# H1DR00.net
KiCad netlist of a schematic drawn in EAGLE
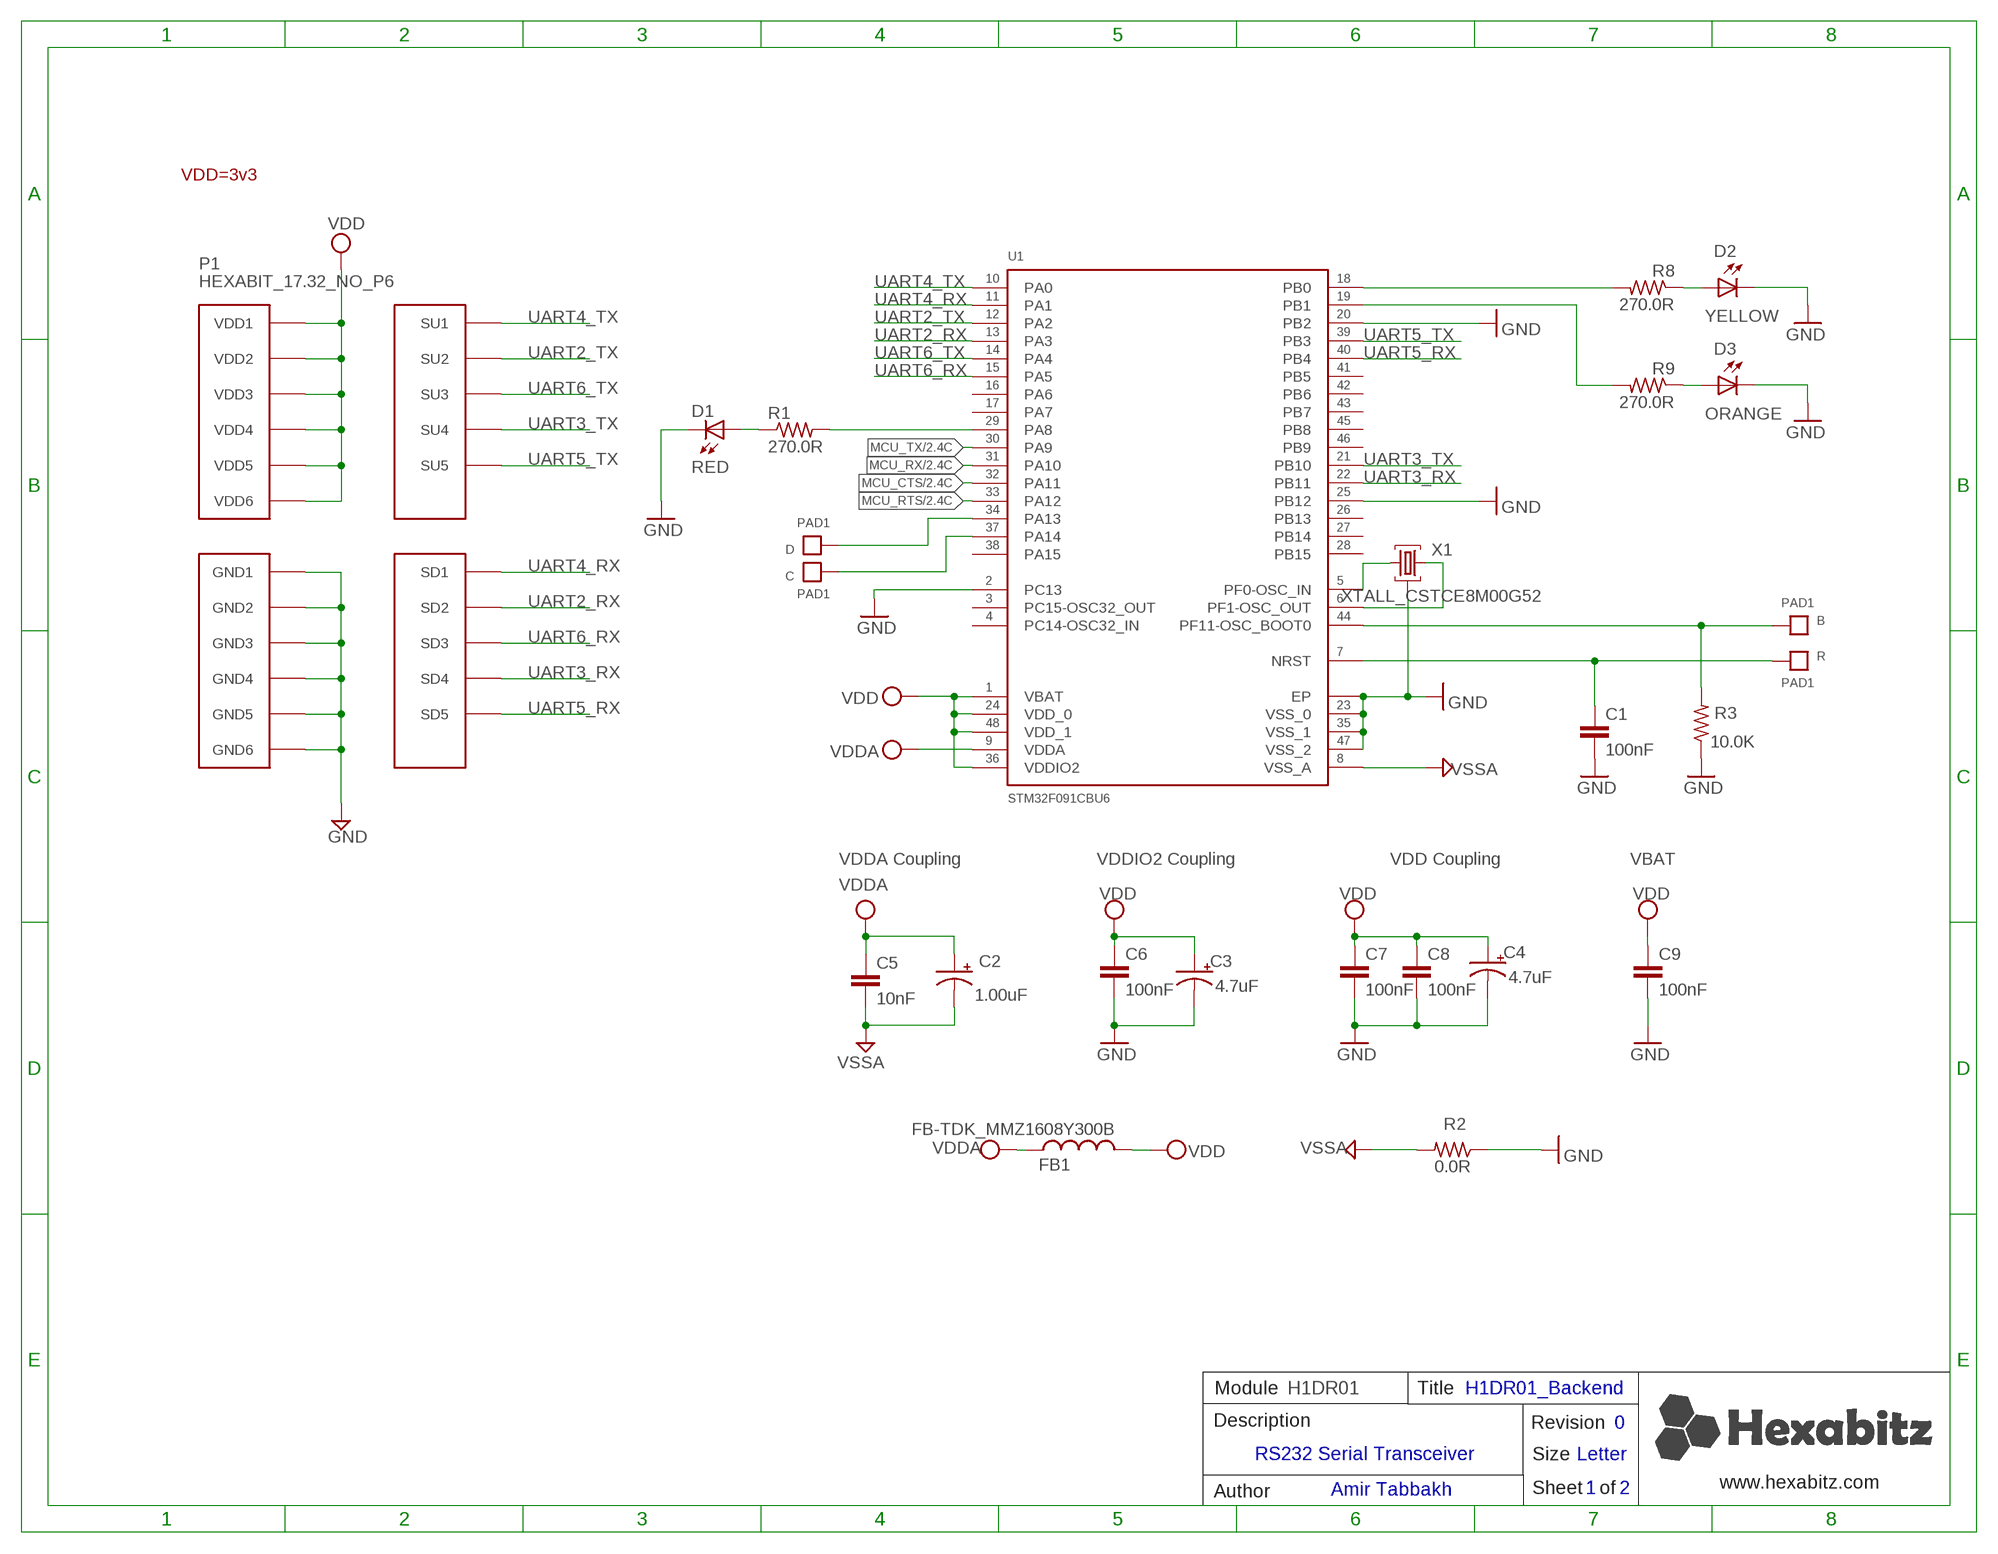
[diagram p0: schematic, sheet 1]
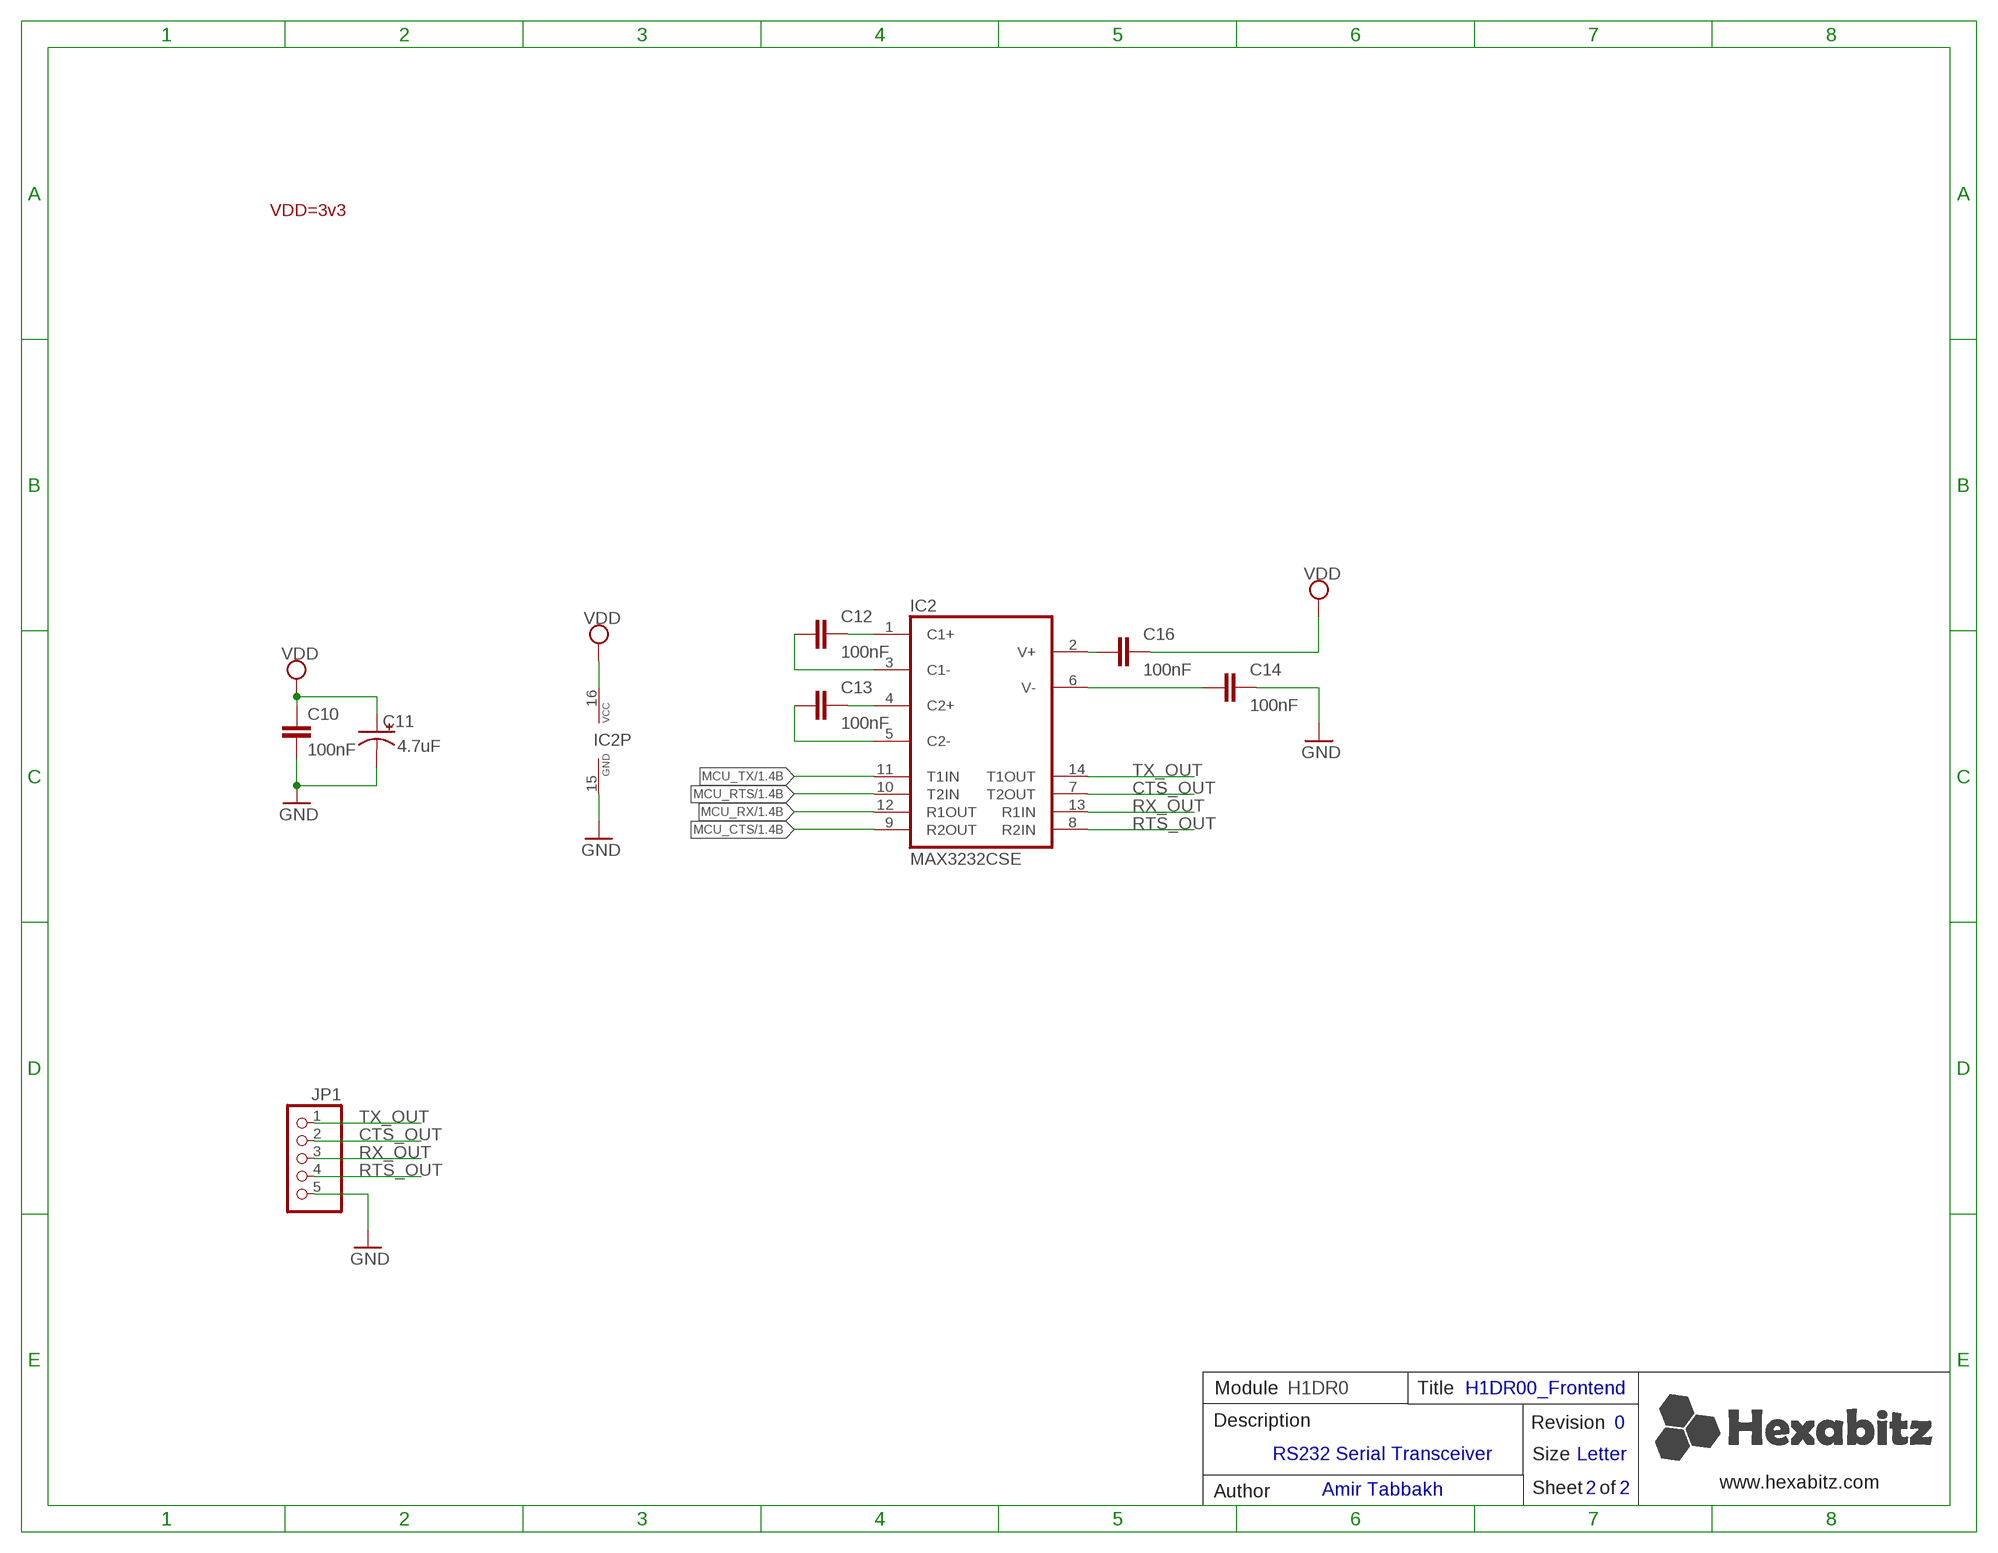
[diagram p1: schematic, sheet 2]

(export (version "E")
  (design (tool "Eeschema 10.0.6"))
  (components
    (comp (ref "C10")
      (value "100nF")
      (footprint "eagle-import:C-0603")
      (fields
        (field (name "CAPACITANCE") "100nF")
        (field (name "MFN") "KEMET")
        (field (name "MPN") "C0603C104K8RACTU")
        (field (name "OCTOPART_URL") "https://octopart.com/c0603c104k8ractu-kemet-145075?r=sp&s=9bS9ASSwSEqMCE9KBEQZ0g")
        (field (name "TOLERANCE") "10%")
        (field (name "VOLTAGE_RATING") "10V")
      )
      (libsource (lib "eagle-import") (part "C-0603"))
    )
    (comp (ref "C11")
      (value "4.7uF")
      (footprint "eagle-import:C-0805-POL")
      (fields
        (field (name "CAPACITANCE") "4.7uF")
        (field (name "MFN") "Murata")
        (field (name "MPN") "GRM21BC81E475KA12L")
        (field (name "OCTOPART_URL") "https://octopart.com/grm21bc81e475ka12l-murata-10331911?r=sp&s=RY3qZSD8T6mG6TC9CHI5qQ")
        (field (name "TOLERANCE") "10%")
        (field (name "VOLTAGE_RATING") "25V")
      )
      (libsource (lib "eagle-import") (part "C-0805-POL"))
    )
    (comp (ref "C12")
      (value "100nF")
      (footprint "eagle-import:C-0603")
      (fields
        (field (name "CAPACITANCE") "100nF")
        (field (name "MFN") "KEMET")
        (field (name "MPN") "C0603C104K8RACTU")
        (field (name "OCTOPART_URL") "https://octopart.com/c0603c104k8ractu-kemet-145075?r=sp&s=9bS9ASSwSEqMCE9KBEQZ0g")
        (field (name "TOLERANCE") "10%")
        (field (name "VOLTAGE_RATING") "10")
      )
      (libsource (lib "eagle-import") (part "C-0603"))
    )
    (comp (ref "C13")
      (value "100nF")
      (footprint "eagle-import:C-0603")
      (fields
        (field (name "CAPACITANCE") "100nF")
        (field (name "MFN") "KEMET")
        (field (name "MPN") "C0603C104K8RACTU")
        (field (name "OCTOPART_URL") "https://octopart.com/c0603c104k8ractu-kemet-145075?r=sp&s=9bS9ASSwSEqMCE9KBEQZ0g")
        (field (name "TOLERANCE") "10%")
        (field (name "VOLTAGE_RATING") "10")
      )
      (libsource (lib "eagle-import") (part "C-0603"))
    )
    (comp (ref "C14")
      (value "100nF")
      (footprint "eagle-import:C-0603")
      (fields
        (field (name "CAPACITANCE") "100nF")
        (field (name "MFN") "KEMET")
        (field (name "MPN") "C0603C104K8RACTU")
        (field (name "OCTOPART_URL") "https://octopart.com/c0603c104k8ractu-kemet-145075?r=sp&s=9bS9ASSwSEqMCE9KBEQZ0g")
        (field (name "TOLERANCE") "10%")
        (field (name "VOLTAGE_RATING") "10")
      )
      (libsource (lib "eagle-import") (part "C-0603"))
    )
    (comp (ref "C16")
      (value "100nF")
      (footprint "eagle-import:C-0603")
      (fields
        (field (name "CAPACITANCE") "100nF")
        (field (name "MFN") "KEMET")
        (field (name "MPN") "C0603C104K8RACTU")
        (field (name "OCTOPART_URL") "https://octopart.com/c0603c104k8ractu-kemet-145075?r=sp&s=9bS9ASSwSEqMCE9KBEQZ0g")
        (field (name "TOLERANCE") "10%")
        (field (name "VOLTAGE_RATING") "10")
      )
      (libsource (lib "eagle-import") (part "C-0603"))
    )
    (comp (ref "IC2")
      (value "MAX3232CSE")
      (footprint "eagle-import:SO16")
      (libsource (lib "eagle-import") (part "MAX3232SEC"))
    )
    (comp (ref "JP1")
      (value "PINHD-1X5/90")
      (footprint "eagle-import:1X05_90")
      (libsource (lib "eagle-import") (part "PINHD-1X5/90"))
    )
    (comp (ref "B")
      (value "PAD1")
      (footprint "eagle-import:PAD1")
      (libsource (lib "eagle-import") (part "PAD1"))
    )
    (comp (ref "C")
      (value "PAD1")
      (footprint "eagle-import:PAD1")
      (libsource (lib "eagle-import") (part "PAD1"))
    )
    (comp (ref "C1")
      (value "100nF")
      (footprint "eagle-import:C-0603")
      (fields
        (field (name "CAPACITANCE") "100nF")
        (field (name "MFN") "KEMET")
        (field (name "MPN") "C0603C104K8RACTU")
        (field (name "OCTOPART_URL") "https://octopart.com/c0603c104k8ractu-kemet-145075?r=sp&s=9bS9ASSwSEqMCE9KBEQZ0g")
        (field (name "TOLERANCE") "10%")
        (field (name "VOLTAGE_RATING") "10V")
      )
      (libsource (lib "eagle-import") (part "C-0603"))
    )
    (comp (ref "C2")
      (value "1.00uF")
      (footprint "eagle-import:C-0805-POL")
      (fields
        (field (name "CAPACITANCE") "1.00uF")
        (field (name "MFN") "Yageo")
        (field (name "MPN") "CC0805KKX7R7BB105")
        (field (name "OCTOPART_URL") "https://octopart.com/cc0805kkx7r7bb105-yageo-8376555?r=sp&s=YKl1wwtkROau_X5nniH2ig")
        (field (name "TOLERANCE") "10%")
        (field (name "VOLTAGE_RATING") "16V")
      )
      (libsource (lib "eagle-import") (part "C-0805-POL"))
    )
    (comp (ref "C3")
      (value "4.7uF")
      (footprint "eagle-import:C-0805-POL")
      (fields
        (field (name "CAPACITANCE") "4.7uF")
        (field (name "MFN") "Murata")
        (field (name "MPN") "GRM21BC81E475KA12L")
        (field (name "OCTOPART_URL") "https://octopart.com/grm21bc81e475ka12l-murata-10331911?r=sp&s=RY3qZSD8T6mG6TC9CHI5qQ")
        (field (name "TOLERANCE") "10%")
        (field (name "VOLTAGE_RATING") "25V")
      )
      (libsource (lib "eagle-import") (part "C-0805-POL"))
    )
    (comp (ref "C4")
      (value "4.7uF")
      (footprint "eagle-import:C-0805-POL")
      (fields
        (field (name "CAPACITANCE") "4.7uF")
        (field (name "MFN") "Murata")
        (field (name "MPN") "GRM21BC81E475KA12L")
        (field (name "OCTOPART_URL") "https://octopart.com/grm21bc81e475ka12l-murata-10331911?r=sp&s=RY3qZSD8T6mG6TC9CHI5qQ")
        (field (name "TOLERANCE") "10%")
        (field (name "VOLTAGE_RATING") "25V")
      )
      (libsource (lib "eagle-import") (part "C-0805-POL"))
    )
    (comp (ref "C5")
      (value "10nF")
      (footprint "eagle-import:C-0603")
      (fields
        (field (name "CAPACITANCE") "10nF")
        (field (name "MFN") "KEMET")
        (field (name "MPN") "C0603C103K5RACTU")
        (field (name "OCTOPART_URL") "https://octopart.com/c0603c103k5ractu-kemet-133094?r=sp&s=R_iPBxLnSmGqhkU2rIMFpg")
        (field (name "TOLERANCE") "10%")
        (field (name "VOLTAGE_RATING") "50V")
      )
      (libsource (lib "eagle-import") (part "C-0603"))
    )
    (comp (ref "C6")
      (value "100nF")
      (footprint "eagle-import:C-0603")
      (fields
        (field (name "CAPACITANCE") "100nF")
        (field (name "MFN") "KEMET")
        (field (name "MPN") "C0603C104K8RACTU")
        (field (name "OCTOPART_URL") "https://octopart.com/c0603c104k8ractu-kemet-145075?r=sp&s=9bS9ASSwSEqMCE9KBEQZ0g")
        (field (name "TOLERANCE") "10%")
        (field (name "VOLTAGE_RATING") "10V")
      )
      (libsource (lib "eagle-import") (part "C-0603"))
    )
    (comp (ref "C7")
      (value "100nF")
      (footprint "eagle-import:C-0603")
      (fields
        (field (name "CAPACITANCE") "100nF")
        (field (name "MFN") "KEMET")
        (field (name "MPN") "C0603C104K8RACTU")
        (field (name "OCTOPART_URL") "https://octopart.com/c0603c104k8ractu-kemet-145075?r=sp&s=9bS9ASSwSEqMCE9KBEQZ0g")
        (field (name "TOLERANCE") "10%")
        (field (name "VOLTAGE_RATING") "10")
      )
      (libsource (lib "eagle-import") (part "C-0603"))
    )
    (comp (ref "C8")
      (value "100nF")
      (footprint "eagle-import:C-0603")
      (fields
        (field (name "CAPACITANCE") "100nF")
        (field (name "MFN") "KEMET")
        (field (name "MPN") "C0603C104K8RACTU")
        (field (name "OCTOPART_URL") "https://octopart.com/c0603c104k8ractu-kemet-145075?r=sp&s=9bS9ASSwSEqMCE9KBEQZ0g")
        (field (name "TOLERANCE") "10%")
        (field (name "VOLTAGE_RATING") "10V")
      )
      (libsource (lib "eagle-import") (part "C-0603"))
    )
    (comp (ref "C9")
      (value "100nF")
      (footprint "eagle-import:C-0603")
      (fields
        (field (name "CAPACITANCE") "100nF")
        (field (name "MFN") "KEMET")
        (field (name "MPN") "C0603C104K8RACTU")
        (field (name "OCTOPART_URL") "https://octopart.com/c0603c104k8ractu-kemet-145075?r=sp&s=9bS9ASSwSEqMCE9KBEQZ0g")
        (field (name "TOLERANCE") "10V")
        (field (name "VOLTAGE_RATING") "10%")
      )
      (libsource (lib "eagle-import") (part "C-0603"))
    )
    (comp (ref "D")
      (value "PAD1")
      (footprint "eagle-import:PAD1")
      (libsource (lib "eagle-import") (part "PAD1"))
    )
    (comp (ref "D1")
      (value "RED")
      (footprint "eagle-import:VLMS1300-GS08")
      (fields
        (field (name "MPN") "VLMS1300-GS08")
        (field (name "MFN") "Vishay")
        (field (name "MPN_1") "VLMS1300-GS08")
        (field (name "OCTOPART_URL") "https://octopart.com/vlms1300-gs08-vishay-21709201?r=sp&s=_gcP4_q8T1SC6PJQPTQ9yA")
      )
      (libsource (lib "eagle-import") (part "VLMS1300-GS08"))
    )
    (comp (ref "D2")
      (value "YELLOW")
      (footprint "eagle-import:VLMS1300-GS08")
      (fields
        (field (name "MPN") "VLMS1300-GS08")
        (field (name "MFN") "Vishay")
        (field (name "MPN_1") "VLMY1300-GS08")
        (field (name "OCTOPART_URL") "https://octopart.com/vlmy1300-gs08-vishay-21709204?r=sp")
      )
      (libsource (lib "eagle-import") (part "VLMS1300-GS08"))
    )
    (comp (ref "D3")
      (value "ORANGE")
      (footprint "eagle-import:VLMS1300-GS08")
      (fields
        (field (name "MPN") "VLMS1300-GS08")
        (field (name "MFN") "Vishay")
        (field (name "MPN_1") "VLMO1300-GS08 ")
        (field (name "OCTOPART_URL") "https://octopart.com/vlmo1300-gs08-vishay-21709200?r=sp#")
      )
      (libsource (lib "eagle-import") (part "VLMS1300-GS08"))
    )
    (comp (ref "FB1")
      (value "FB-TDK_MMZ1608Y300B")
      (footprint "eagle-import:FB-TDK_MMZ1608Y300B")
      (fields
        (field (name "MFN") "TDK ")
        (field (name "MPN") "MMZ1608Y300B")
        (field (name "OCTOPART_URL") "https://octopart.com/mmz1608y300b-tdk-368280?r=sp&s=cd9_2ZEqQ9q9UNBuQgHAiA")
      )
      (libsource (lib "eagle-import") (part "FB-TDK_MMZ1608Y300B"))
    )
    (comp (ref "P1")
      (value "HEXABIT_17.32_NO_P6")
      (footprint "eagle-import:HEXABIT_17.32_NO_P6")
      (libsource (lib "eagle-import") (part "HEXABIT_?_NO_P617.32"))
    )
    (comp (ref "R")
      (value "PAD1")
      (footprint "eagle-import:PAD1")
      (libsource (lib "eagle-import") (part "PAD1"))
    )
    (comp (ref "R1")
      (value "270.0R")
      (footprint "eagle-import:R-0603")
      (fields
        (field (name "MFN") "Yageo")
        (field (name "MPN") "RC0603FR-07270RL")
        (field (name "OCTOPART_URL") "https://octopart.com/search?q=RC0603FR-07270RL&start=0")
        (field (name "RESISTANCE") "270.0 Ohm")
        (field (name "TOLERANCE") "1%")
      )
      (libsource (lib "eagle-import") (part "R-0603"))
    )
    (comp (ref "R2")
      (value "0.0R")
      (footprint "eagle-import:R-0603")
      (fields
        (field (name "MFN") "Yageo")
        (field (name "MPN") "RC0603JR-070RL")
        (field (name "OCTOPART_URL") "https://octopart.com/rc0603jr-070rl-yageo-1241539?r=sp&s=X2NteqRjRNWrnx42Y0aliA")
        (field (name "RESISTANCE") "0.0 Ohm")
      )
      (libsource (lib "eagle-import") (part "R-0603"))
    )
    (comp (ref "R3")
      (value "10.0K")
      (footprint "eagle-import:R-0603")
      (fields
        (field (name "MFN") "Yageo")
        (field (name "MPN") "RC0603JR-0710KL")
        (field (name "OCTOPART_URL") "https://octopart.com/search?q=RC0603JR-0710KL&start=0")
        (field (name "RESISTANCE") "10.0K Ohm")
        (field (name "TOLERANCE") "5%")
      )
      (libsource (lib "eagle-import") (part "R-0603"))
    )
    (comp (ref "R8")
      (value "270.0R")
      (footprint "eagle-import:R-0603")
      (fields
        (field (name "MFN") "Yageo")
        (field (name "MPN") "RC0603FR-07270RL")
        (field (name "OCTOPART_URL") "https://octopart.com/search?q=RC0603FR-07270RL&start=0")
        (field (name "RESISTANCE") "270.0 Ohm")
        (field (name "TOLERANCE") "1%")
      )
      (libsource (lib "eagle-import") (part "R-0603"))
    )
    (comp (ref "R9")
      (value "270.0R")
      (footprint "eagle-import:R-0603")
      (fields
        (field (name "MFN") "Yageo")
        (field (name "MPN") "RC0603FR-07270RL")
        (field (name "OCTOPART_URL") "https://octopart.com/search?q=RC0603FR-07270RL&start=0")
        (field (name "RESISTANCE") "270.0 Ohm")
        (field (name "TOLERANCE") "1%")
      )
      (libsource (lib "eagle-import") (part "R-0603"))
    )
    (comp (ref "U1")
      (value "STM32F091CBU6")
      (footprint "eagle-import:STM32F091CBU6")
      (libsource (lib "eagle-import") (part "STM32F091CBU6"))
    )
    (comp (ref "X1")
      (value "XTALL_CSTCE8M00G52")
      (footprint "eagle-import:XTALL_CSTCE8M00G52")
      (fields (field (name "MPN") "CSTCE8M00G52Z-R0"))
      (libsource (lib "eagle-import") (part "XTALL_CSTCE8M00G52"))
    )
  )
  (nets
    (net (code "1") (name "CTS_OUT") (class "Default")
      (node (ref "IC2") (pin "7") (pinfunction "T2OUT_7") (pintype "output"))
      (node (ref "JP1") (pin "2") (pinfunction "2_2") (pintype "passive"))
    )
    (net (code "2") (name "GND") (class "Default")
      (node (ref "C1") (pin "2") (pinfunction "2_2") (pintype "passive"))
      (node (ref "C10") (pin "2") (pinfunction "2_2") (pintype "passive"))
      (node (ref "C11") (pin "2") (pinfunction "-_2") (pintype "passive"))
      (node (ref "C14") (pin "2") (pinfunction "2_2") (pintype "passive"))
      (node (ref "C3") (pin "2") (pinfunction "-_2") (pintype "passive"))
      (node (ref "C4") (pin "2") (pinfunction "-_2") (pintype "passive"))
      (node (ref "C6") (pin "2") (pinfunction "2_2") (pintype "passive"))
      (node (ref "C7") (pin "2") (pinfunction "2_2") (pintype "passive"))
      (node (ref "C8") (pin "2") (pinfunction "2_2") (pintype "passive"))
      (node (ref "C9") (pin "2") (pinfunction "2_2") (pintype "passive"))
      (node (ref "D1") (pin "C") (pinfunction "C_C") (pintype "passive"))
      (node (ref "D2") (pin "C") (pinfunction "C_C") (pintype "passive"))
      (node (ref "D3") (pin "C") (pinfunction "C_C") (pintype "passive"))
      (node (ref "IC2") (pin "15") (pinfunction "GND_15") (pintype "power_in"))
      (node (ref "JP1") (pin "5") (pinfunction "5_5") (pintype "passive"))
      (node (ref "P1") (pin "PAD_PD10") (pinfunction "GND4_PAD_PD10") (pintype "power_in"))
      (node (ref "P1") (pin "PAD_PD11") (pinfunction "GND5_PAD_PD11") (pintype "power_in"))
      (node (ref "P1") (pin "PAD_PD12") (pinfunction "GND6_PAD_PD12") (pintype "power_in"))
      (node (ref "P1") (pin "PAD_PD7") (pinfunction "GND1_PAD_PD7") (pintype "power_in"))
      (node (ref "P1") (pin "PAD_PD8") (pinfunction "GND2_PAD_PD8") (pintype "power_in"))
      (node (ref "P1") (pin "PAD_PD9") (pinfunction "GND3_PAD_PD9") (pintype "power_in"))
      (node (ref "R2") (pin "1") (pinfunction "1_1") (pintype "passive"))
      (node (ref "R3") (pin "1") (pinfunction "1_1") (pintype "passive"))
      (node (ref "U1") (pin "EP") (pinfunction "EP_EP") (pintype "power_in"))
      (node (ref "U1") (pin "P$2") (pinfunction "PC13_P$2") (pintype "bidirectional"))
      (node (ref "U1") (pin "P$20") (pinfunction "PB2_P$20") (pintype "bidirectional"))
      (node (ref "U1") (pin "P$23") (pinfunction "VSS_0_P$23") (pintype "power_in"))
      (node (ref "U1") (pin "P$25") (pinfunction "PB12_P$25") (pintype "bidirectional"))
      (node (ref "U1") (pin "P$35") (pinfunction "VSS_1_P$35") (pintype "power_in"))
      (node (ref "U1") (pin "P$47") (pinfunction "VSS_2_P$47") (pintype "power_in"))
      (node (ref "X1") (pin "P$2") (pinfunction "2_P$2") (pintype "passive"))
    )
    (net (code "3") (name "MCU_CTS") (class "Default")
      (node (ref "IC2") (pin "9") (pinfunction "R2OUT_9") (pintype "output"))
      (node (ref "U1") (pin "P$32") (pinfunction "PA11_P$32") (pintype "bidirectional"))
    )
    (net (code "4") (name "MCU_RTS") (class "Default")
      (node (ref "IC2") (pin "10") (pinfunction "T2IN_10") (pintype "input"))
      (node (ref "U1") (pin "P$33") (pinfunction "PA12_P$33") (pintype "bidirectional"))
    )
    (net (code "5") (name "MCU_RX") (class "Default")
      (node (ref "IC2") (pin "12") (pinfunction "R1OUT_12") (pintype "output"))
      (node (ref "U1") (pin "P$31") (pinfunction "PA10_P$31") (pintype "bidirectional"))
    )
    (net (code "6") (name "MCU_TX") (class "Default")
      (node (ref "IC2") (pin "11") (pinfunction "T1IN_11") (pintype "input"))
      (node (ref "U1") (pin "P$30") (pinfunction "PA9_P$30") (pintype "bidirectional"))
    )
    (net (code "7") (name "Net-(D1-PadA)") (class "Default")
      (node (ref "D1") (pin "A") (pinfunction "A_A") (pintype "passive"))
      (node (ref "R1") (pin "1") (pinfunction "1_1") (pintype "passive"))
    )
    (net (code "8") (name "Net-(D2-PadA)") (class "Default")
      (node (ref "D2") (pin "A") (pinfunction "A_A") (pintype "passive"))
      (node (ref "R8") (pin "1") (pinfunction "1_1") (pintype "passive"))
    )
    (net (code "9") (name "Net-(D3-PadA)") (class "Default")
      (node (ref "D3") (pin "A") (pinfunction "A_A") (pintype "passive"))
      (node (ref "R9") (pin "1") (pinfunction "1_1") (pintype "passive"))
    )
    (net (code "10") (name "Net-(IC2A-C1+)") (class "Default")
      (node (ref "C12") (pin "2") (pinfunction "2_2") (pintype "passive"))
      (node (ref "IC2") (pin "1") (pinfunction "C1+_1") (pintype "bidirectional"))
    )
    (net (code "11") (name "Net-(IC2A-C1-)") (class "Default")
      (node (ref "C12") (pin "1") (pinfunction "1_1") (pintype "passive"))
      (node (ref "IC2") (pin "3") (pinfunction "C1-_3") (pintype "bidirectional"))
    )
    (net (code "12") (name "Net-(IC2A-C2+)") (class "Default")
      (node (ref "C13") (pin "2") (pinfunction "2_2") (pintype "passive"))
      (node (ref "IC2") (pin "4") (pinfunction "C2+_4") (pintype "bidirectional"))
    )
    (net (code "13") (name "Net-(IC2A-C2-)") (class "Default")
      (node (ref "C13") (pin "1") (pinfunction "1_1") (pintype "passive"))
      (node (ref "IC2") (pin "5") (pinfunction "C2-_5") (pintype "bidirectional"))
    )
    (net (code "14") (name "Net-(IC2A-V+)") (class "Default")
      (node (ref "C16") (pin "1") (pinfunction "1_1") (pintype "passive"))
      (node (ref "IC2") (pin "2") (pinfunction "V+_2") (pintype "bidirectional"))
    )
    (net (code "15") (name "Net-(IC2A-V-)") (class "Default")
      (node (ref "C14") (pin "1") (pinfunction "1_1") (pintype "passive"))
      (node (ref "IC2") (pin "6") (pinfunction "V-_6") (pintype "bidirectional"))
    )
    (net (code "16") (name "Net-(U1-NRST)") (class "Default")
      (node (ref "C1") (pin "1") (pinfunction "1_1") (pintype "passive"))
      (node (ref "R") (pin "P$1") (pinfunction "P$1_P$1") (pintype "passive"))
      (node (ref "R") (pin "P$2") (pinfunction "P$1_P$2") (pintype "passive"))
      (node (ref "U1") (pin "P$7") (pinfunction "NRST_P$7") (pintype "passive"))
    )
    (net (code "17") (name "Net-(U1-PA8)") (class "Default")
      (node (ref "R1") (pin "2") (pinfunction "2_2") (pintype "passive"))
      (node (ref "U1") (pin "P$29") (pinfunction "PA8_P$29") (pintype "bidirectional"))
    )
    (net (code "18") (name "Net-(U1-PA13)") (class "Default")
      (node (ref "D") (pin "P$1") (pinfunction "P$1_P$1") (pintype "passive"))
      (node (ref "D") (pin "P$2") (pinfunction "P$1_P$2") (pintype "passive"))
      (node (ref "U1") (pin "P$34") (pinfunction "PA13_P$34") (pintype "bidirectional"))
    )
    (net (code "19") (name "Net-(U1-PA14)") (class "Default")
      (node (ref "C") (pin "P$1") (pinfunction "P$1_P$1") (pintype "passive"))
      (node (ref "C") (pin "P$2") (pinfunction "P$1_P$2") (pintype "passive"))
      (node (ref "U1") (pin "P$37") (pinfunction "PA14_P$37") (pintype "bidirectional"))
    )
    (net (code "20") (name "Net-(U1-PB0)") (class "Default")
      (node (ref "R8") (pin "2") (pinfunction "2_2") (pintype "passive"))
      (node (ref "U1") (pin "P$18") (pinfunction "PB0_P$18") (pintype "bidirectional"))
    )
    (net (code "21") (name "Net-(U1-PB1)") (class "Default")
      (node (ref "R9") (pin "2") (pinfunction "2_2") (pintype "passive"))
      (node (ref "U1") (pin "P$19") (pinfunction "PB1_P$19") (pintype "bidirectional"))
    )
    (net (code "22") (name "Net-(U1-PF0-OSC_IN)") (class "Default")
      (node (ref "U1") (pin "P$5") (pinfunction "PF0-OSC_IN_P$5") (pintype "bidirectional"))
      (node (ref "X1") (pin "P$1") (pinfunction "1_P$1") (pintype "passive"))
    )
    (net (code "23") (name "Net-(U1-PF1-OSC_OUT)") (class "Default")
      (node (ref "U1") (pin "P$6") (pinfunction "PF1-OSC_OUT_P$6") (pintype "bidirectional"))
      (node (ref "X1") (pin "P$3") (pinfunction "3_P$3") (pintype "passive"))
    )
    (net (code "24") (name "Net-(U1-PF11-OSC_BOOT0)") (class "Default")
      (node (ref "B") (pin "P$1") (pinfunction "P$1_P$1") (pintype "passive"))
      (node (ref "B") (pin "P$2") (pinfunction "P$1_P$2") (pintype "passive"))
      (node (ref "R3") (pin "2") (pinfunction "2_2") (pintype "passive"))
      (node (ref "U1") (pin "P$44") (pinfunction "PF11-OSC_BOOT0_P$44") (pintype "bidirectional"))
    )
    (net (code "25") (name "RTS_OUT") (class "Default")
      (node (ref "IC2") (pin "8") (pinfunction "R2IN_8") (pintype "input"))
      (node (ref "JP1") (pin "4") (pinfunction "4_4") (pintype "passive"))
    )
    (net (code "26") (name "RX_OUT") (class "Default")
      (node (ref "IC2") (pin "13") (pinfunction "R1IN_13") (pintype "input"))
      (node (ref "JP1") (pin "3") (pinfunction "3_3") (pintype "passive"))
    )
    (net (code "27") (name "TX_OUT") (class "Default")
      (node (ref "IC2") (pin "14") (pinfunction "T1OUT_14") (pintype "output"))
      (node (ref "JP1") (pin "1") (pinfunction "1_1") (pintype "passive"))
    )
    (net (code "28") (name "UART2_RX") (class "Default")
      (node (ref "P1") (pin "PAD_PD2") (pinfunction "SD2_PAD_PD2") (pintype "bidirectional"))
      (node (ref "U1") (pin "P$13") (pinfunction "PA3_P$13") (pintype "bidirectional"))
    )
    (net (code "29") (name "UART2_TX") (class "Default")
      (node (ref "P1") (pin "PAD_PU2") (pinfunction "SU2_PAD_PU2") (pintype "bidirectional"))
      (node (ref "U1") (pin "P$12") (pinfunction "PA2_P$12") (pintype "bidirectional"))
    )
    (net (code "30") (name "UART3_RX") (class "Default")
      (node (ref "P1") (pin "PAD_PD4") (pinfunction "SD4_PAD_PD4") (pintype "bidirectional"))
      (node (ref "U1") (pin "P$22") (pinfunction "PB11_P$22") (pintype "bidirectional"))
    )
    (net (code "31") (name "UART3_TX") (class "Default")
      (node (ref "P1") (pin "PAD_PU4") (pinfunction "SU4_PAD_PU4") (pintype "bidirectional"))
      (node (ref "U1") (pin "P$21") (pinfunction "PB10_P$21") (pintype "bidirectional"))
    )
    (net (code "32") (name "UART4_RX") (class "Default")
      (node (ref "P1") (pin "PAD_PD1") (pinfunction "SD1_PAD_PD1") (pintype "bidirectional"))
      (node (ref "U1") (pin "P$11") (pinfunction "PA1_P$11") (pintype "bidirectional"))
    )
    (net (code "33") (name "UART4_TX") (class "Default")
      (node (ref "P1") (pin "PAD_PU1") (pinfunction "SU1_PAD_PU1") (pintype "bidirectional"))
      (node (ref "U1") (pin "P$10") (pinfunction "PA0_P$10") (pintype "bidirectional"))
    )
    (net (code "34") (name "UART5_RX") (class "Default")
      (node (ref "P1") (pin "PAD_PD5") (pinfunction "SD5_PAD_PD5") (pintype "bidirectional"))
      (node (ref "U1") (pin "P$40") (pinfunction "PB4_P$40") (pintype "bidirectional"))
    )
    (net (code "35") (name "UART5_TX") (class "Default")
      (node (ref "P1") (pin "PAD_PU5") (pinfunction "SU5_PAD_PU5") (pintype "bidirectional"))
      (node (ref "U1") (pin "P$39") (pinfunction "PB3_P$39") (pintype "bidirectional"))
    )
    (net (code "36") (name "UART6_RX") (class "Default")
      (node (ref "P1") (pin "PAD_PD3") (pinfunction "SD3_PAD_PD3") (pintype "bidirectional"))
      (node (ref "U1") (pin "P$15") (pinfunction "PA5_P$15") (pintype "bidirectional"))
    )
    (net (code "37") (name "UART6_TX") (class "Default")
      (node (ref "P1") (pin "PAD_PU3") (pinfunction "SU3_PAD_PU3") (pintype "bidirectional"))
      (node (ref "U1") (pin "P$14") (pinfunction "PA4_P$14") (pintype "bidirectional"))
    )
    (net (code "38") (name "VDD") (class "Default")
      (node (ref "C10") (pin "1") (pinfunction "1_1") (pintype "passive"))
      (node (ref "C11") (pin "1") (pinfunction "+_1") (pintype "passive"))
      (node (ref "C16") (pin "2") (pinfunction "2_2") (pintype "passive"))
      (node (ref "C3") (pin "1") (pinfunction "+_1") (pintype "passive"))
      (node (ref "C4") (pin "1") (pinfunction "+_1") (pintype "passive"))
      (node (ref "C6") (pin "1") (pinfunction "1_1") (pintype "passive"))
      (node (ref "C7") (pin "1") (pinfunction "1_1") (pintype "passive"))
      (node (ref "C8") (pin "1") (pinfunction "1_1") (pintype "passive"))
      (node (ref "C9") (pin "1") (pinfunction "1_1") (pintype "passive"))
      (node (ref "FB1") (pin "2") (pinfunction "2_2") (pintype "passive"))
      (node (ref "IC2") (pin "16") (pinfunction "VCC_16") (pintype "power_in"))
      (node (ref "P1") (pin "PAD_PU10") (pinfunction "VDD4_PAD_PU10") (pintype "power_in"))
      (node (ref "P1") (pin "PAD_PU11") (pinfunction "VDD5_PAD_PU11") (pintype "power_in"))
      (node (ref "P1") (pin "PAD_PU12") (pinfunction "VDD6_PAD_PU12") (pintype "power_in"))
      (node (ref "P1") (pin "PAD_PU7") (pinfunction "VDD1_PAD_PU7") (pintype "power_in"))
      (node (ref "P1") (pin "PAD_PU8") (pinfunction "VDD2_PAD_PU8") (pintype "power_in"))
      (node (ref "P1") (pin "PAD_PU9") (pinfunction "VDD3_PAD_PU9") (pintype "power_in"))
      (node (ref "U1") (pin "P$1") (pinfunction "VBAT_P$1") (pintype "power_in"))
      (node (ref "U1") (pin "P$24") (pinfunction "VDD_0_P$24") (pintype "power_in"))
      (node (ref "U1") (pin "P$36") (pinfunction "VDDIO2_P$36") (pintype "power_in"))
      (node (ref "U1") (pin "P$48") (pinfunction "VDD_1_P$48") (pintype "power_in"))
    )
    (net (code "39") (name "VDDA") (class "Default")
      (node (ref "C2") (pin "1") (pinfunction "+_1") (pintype "passive"))
      (node (ref "C5") (pin "1") (pinfunction "1_1") (pintype "passive"))
      (node (ref "FB1") (pin "1") (pinfunction "1_1") (pintype "passive"))
      (node (ref "U1") (pin "P$9") (pinfunction "VDDA_P$9") (pintype "power_in"))
    )
    (net (code "40") (name "VSSA") (class "Default")
      (node (ref "C2") (pin "2") (pinfunction "-_2") (pintype "passive"))
      (node (ref "C5") (pin "2") (pinfunction "2_2") (pintype "passive"))
      (node (ref "R2") (pin "2") (pinfunction "2_2") (pintype "passive"))
      (node (ref "U1") (pin "P$8") (pinfunction "VSS_A_P$8") (pintype "power_in"))
    )
    (net (code "41") (name "unconnected-(U1-PA6-PadP$16)") (class "Default")
      (node (ref "U1") (pin "P$16") (pinfunction "PA6_P$16") (pintype "bidirectional"))
    )
    (net (code "42") (name "unconnected-(U1-PA7-PadP$17)") (class "Default")
      (node (ref "U1") (pin "P$17") (pinfunction "PA7_P$17") (pintype "bidirectional"))
    )
    (net (code "43") (name "unconnected-(U1-PA15-PadP$38)") (class "Default")
      (node (ref "U1") (pin "P$38") (pinfunction "PA15_P$38") (pintype "bidirectional"))
    )
    (net (code "44") (name "unconnected-(U1-PB5-PadP$41)") (class "Default")
      (node (ref "U1") (pin "P$41") (pinfunction "PB5_P$41") (pintype "bidirectional"))
    )
    (net (code "45") (name "unconnected-(U1-PB6-PadP$42)") (class "Default")
      (node (ref "U1") (pin "P$42") (pinfunction "PB6_P$42") (pintype "bidirectional"))
    )
    (net (code "46") (name "unconnected-(U1-PB7-PadP$43)") (class "Default")
      (node (ref "U1") (pin "P$43") (pinfunction "PB7_P$43") (pintype "bidirectional"))
    )
    (net (code "47") (name "unconnected-(U1-PB8-PadP$45)") (class "Default")
      (node (ref "U1") (pin "P$45") (pinfunction "PB8_P$45") (pintype "bidirectional"))
    )
    (net (code "48") (name "unconnected-(U1-PB9-PadP$46)") (class "Default")
      (node (ref "U1") (pin "P$46") (pinfunction "PB9_P$46") (pintype "bidirectional"))
    )
    (net (code "49") (name "unconnected-(U1-PB13-PadP$26)") (class "Default")
      (node (ref "U1") (pin "P$26") (pinfunction "PB13_P$26") (pintype "bidirectional"))
    )
    (net (code "50") (name "unconnected-(U1-PB14-PadP$27)") (class "Default")
      (node (ref "U1") (pin "P$27") (pinfunction "PB14_P$27") (pintype "bidirectional"))
    )
    (net (code "51") (name "unconnected-(U1-PB15-PadP$28)") (class "Default")
      (node (ref "U1") (pin "P$28") (pinfunction "PB15_P$28") (pintype "bidirectional"))
    )
    (net (code "52") (name "unconnected-(U1-PC14-OSC32_IN-PadP$3)") (class "Default")
      (node (ref "U1") (pin "P$3") (pinfunction "PC14-OSC32_IN_P$3") (pintype "bidirectional"))
    )
    (net (code "53") (name "unconnected-(U1-PC15-OSC32_OUT-PadP$4)") (class "Default")
      (node (ref "U1") (pin "P$4") (pinfunction "PC15-OSC32_OUT_P$4") (pintype "bidirectional"))
    )
  )
)
